# ArduinoV1Sch.net
KiCad netlist of a schematic drawn in Altium Designer
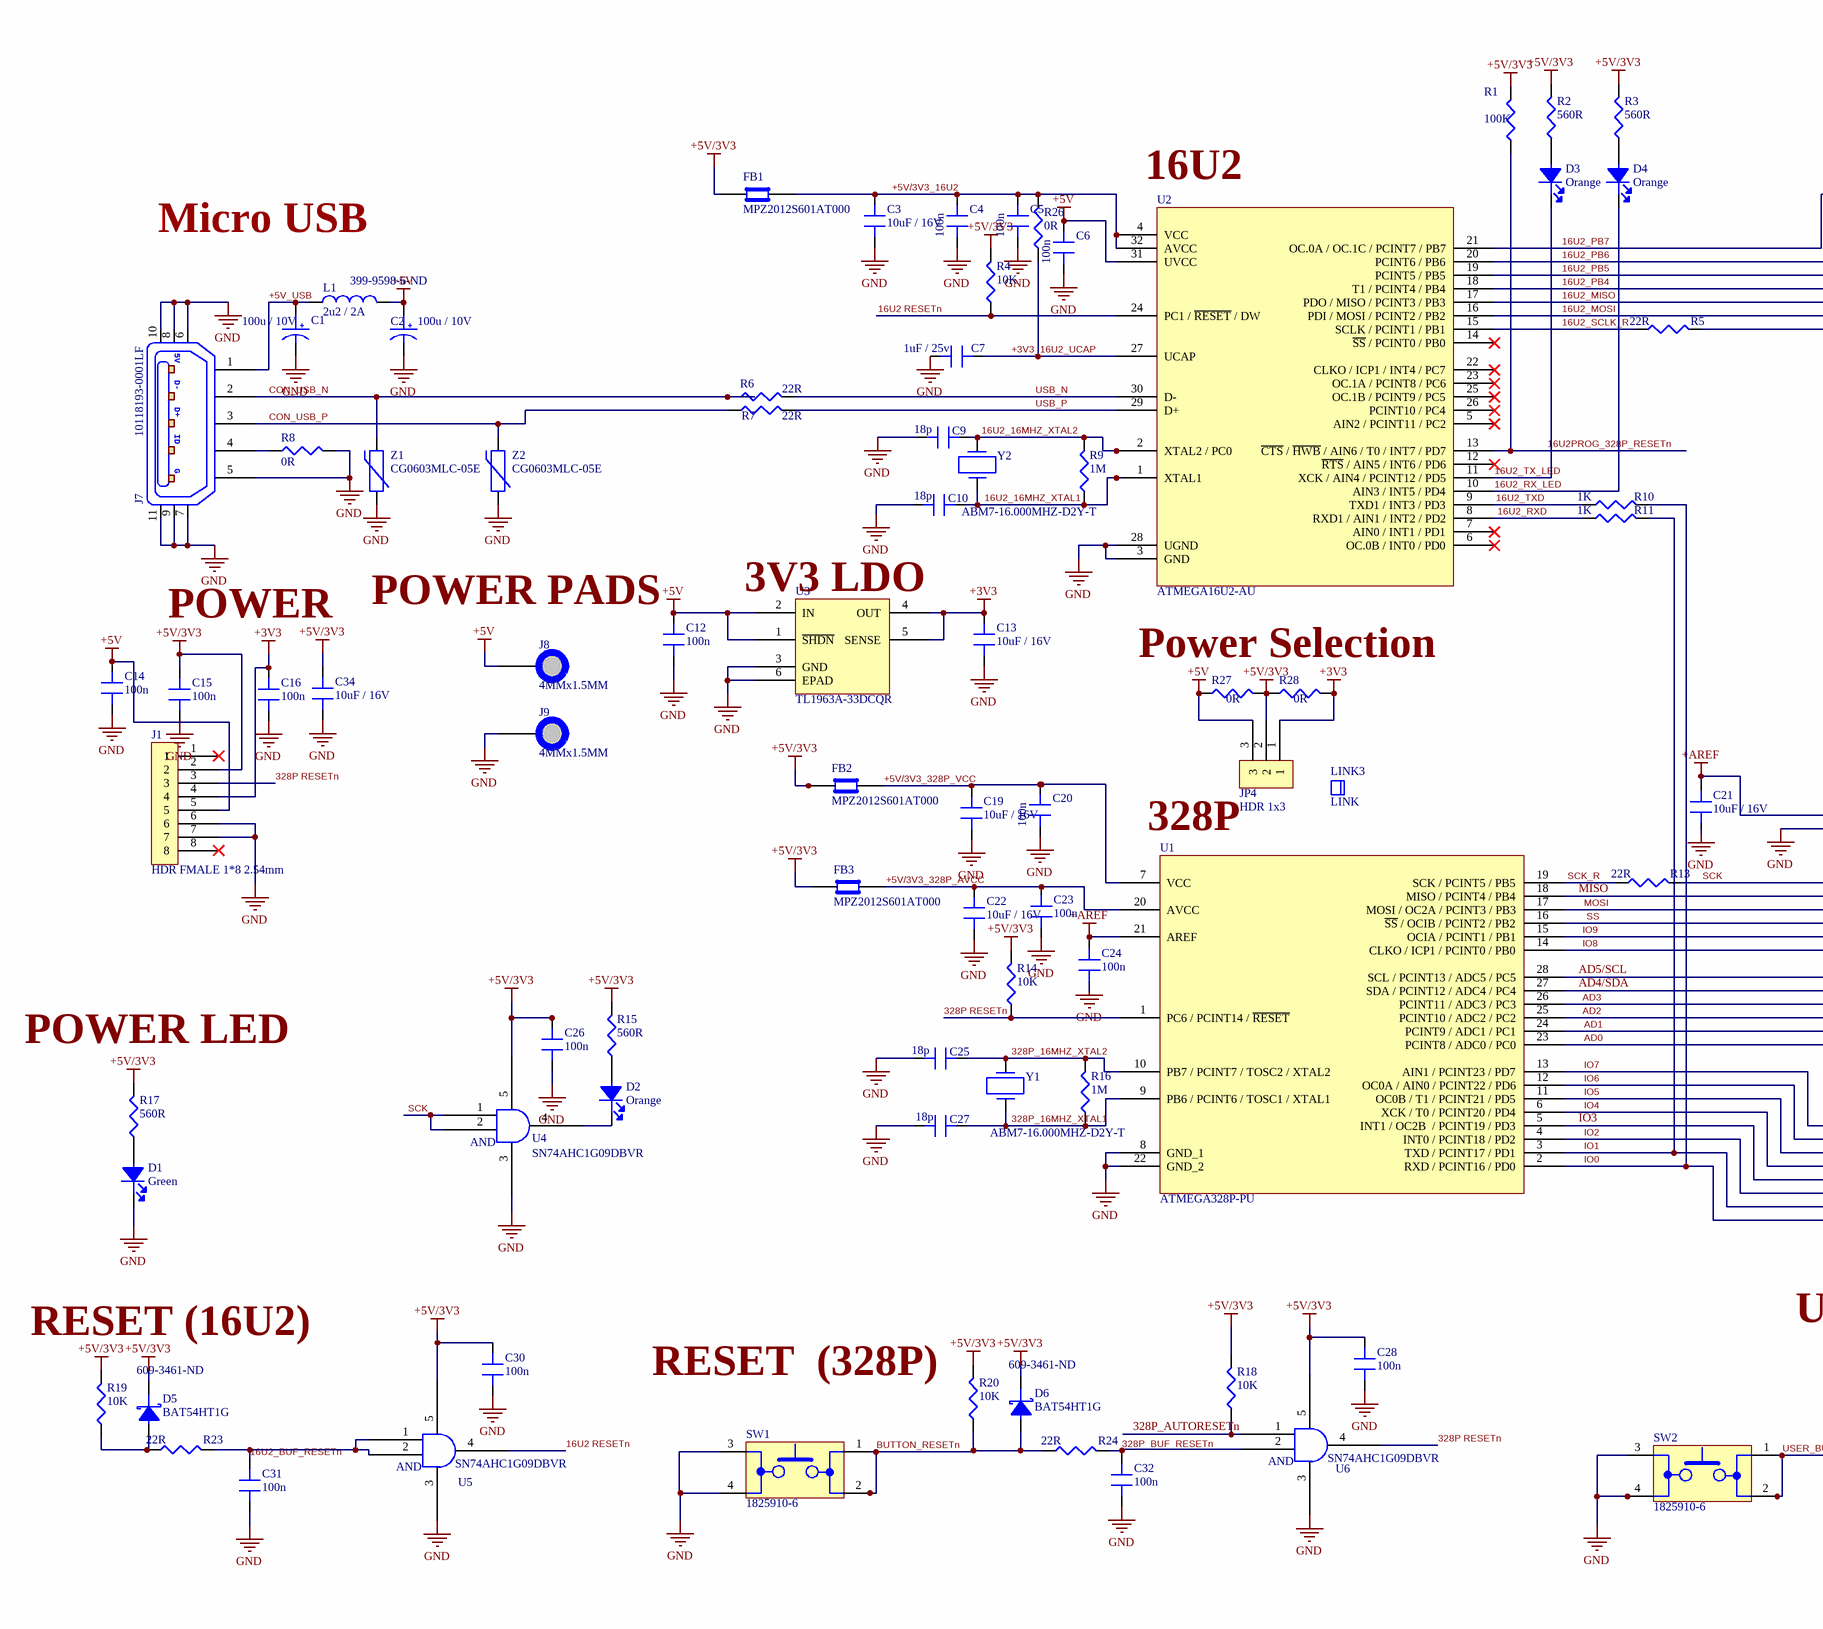
[diagram p0: ArduinoV1Sch.SchDoc, left]
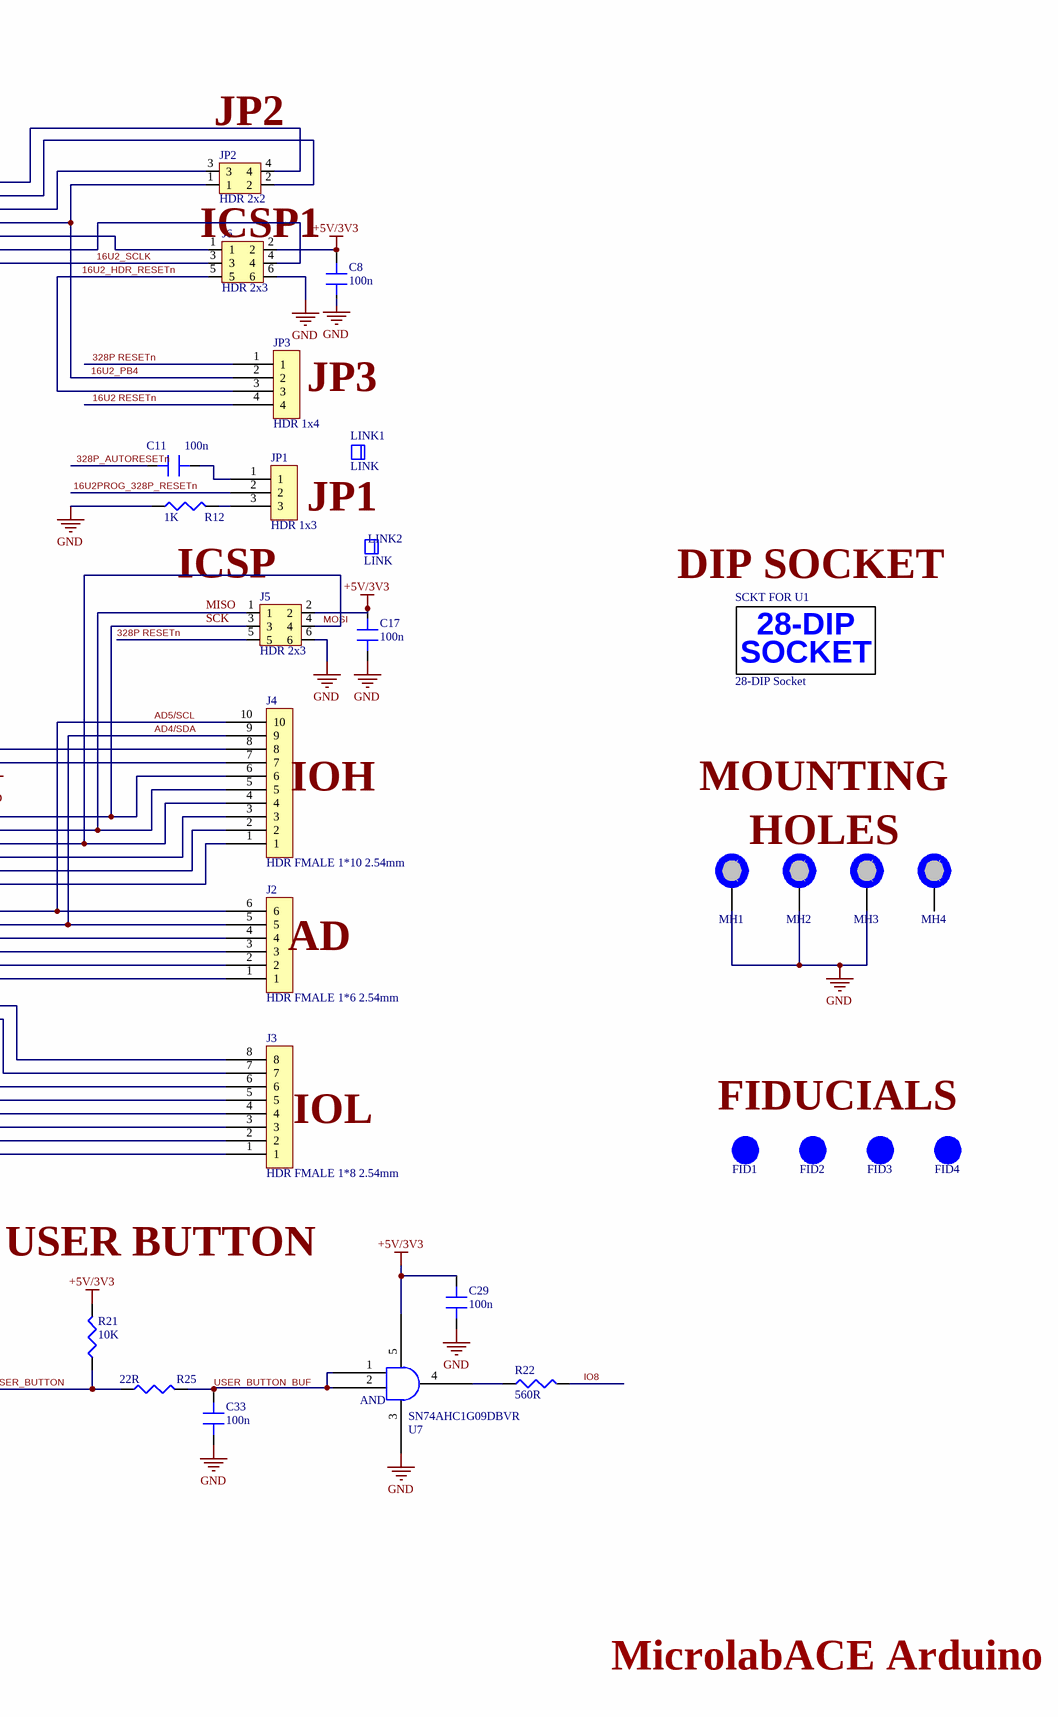
[diagram p1: ArduinoV1Sch.SchDoc, right]

(export (version "E")
  (design (tool "Eeschema 10.0.6"))
  (components
    (comp (ref "C1")
      (value "100u / 10V")
      (footprint "C_ALU_C_SIZE")
      (description "Cap Aluminum 100uF 10V 20% (5 X 5.4mm) SMD 50mA 1000 hr 85°C T/R")
      (fields
        (field (name "MANUFACTURER") "Panasonic")
        (field (name "MANUFACTURER PART NUMBER") "EEE-1AA101WR")
      )
      (libsource (lib "ArduinoV1Sch") (part "EEE-1AA101WR"))
    )
    (comp (ref "C2")
      (value "100u / 10V")
      (footprint "C_ALU_C_SIZE")
      (description "Cap Aluminum 100uF 10V 20% (5 X 5.4mm) SMD 50mA 1000 hr 85°C T/R")
      (fields
        (field (name "MANUFACTURER") "Panasonic")
        (field (name "MANUFACTURER PART NUMBER") "EEE-1AA101WR")
      )
      (libsource (lib "ArduinoV1Sch") (part "EEE-1AA101WR"))
    )
    (comp (ref "C3")
      (value "10uF / 16V")
      (footprint "C0805")
      (description "CAP CER 10UF 16V X5R 0805")
      (fields
        (field (name "MANUFACTURER") "TDK")
        (field (name "MANUFACTURER PART NUMBER") "CGA4J1X5R1C106M125AC")
      )
      (libsource (lib "ArduinoV1Sch") (part "CGA4J1X5R1C106M125AC"))
    )
    (comp (ref "C4")
      (value "100n")
      (footprint "C0805")
      (description "CAP CER 0.1UF 50V X7R 0805")
      (fields
        (field (name "MANUFACTURER") "TDK")
        (field (name "MANUFACTURER PART NUMBER") "C2012X7R1H104K085AA")
      )
      (libsource (lib "ArduinoV1Sch") (part "C2012X7R1H104K085AA"))
    )
    (comp (ref "C5")
      (value "100n")
      (footprint "C0805")
      (description "CAP CER 0.1UF 50V X7R 0805")
      (fields
        (field (name "MANUFACTURER") "TDK")
        (field (name "MANUFACTURER PART NUMBER") "C2012X7R1H104K085AA")
      )
      (libsource (lib "ArduinoV1Sch") (part "C2012X7R1H104K085AA"))
    )
    (comp (ref "C6")
      (value "100n")
      (footprint "C0805")
      (description "CAP CER 0.1UF 50V X7R 0805")
      (fields
        (field (name "MANUFACTURER") "TDK")
        (field (name "MANUFACTURER PART NUMBER") "C2012X7R1H104K085AA")
      )
      (libsource (lib "ArduinoV1Sch") (part "C2012X7R1H104K085AA"))
    )
    (comp (ref "C7")
      (value "1uF / 25v")
      (footprint "C0805")
      (description "CAP CER 1UF 25V X5R 0805")
      (fields
        (field (name "MANUFACTURER") "TDK")
        (field (name "MANUFACTURER PART NUMBER") "C2012X5R1E105K125AA")
      )
      (libsource (lib "ArduinoV1Sch") (part "C2012X5R1E105K125AA"))
    )
    (comp (ref "C8")
      (value "100n")
      (footprint "C0805")
      (description "CAP CER 0.1UF 50V X7R 0805")
      (fields
        (field (name "MANUFACTURER") "TDK")
        (field (name "MANUFACTURER PART NUMBER") "C2012X7R1H104K085AA")
      )
      (libsource (lib "ArduinoV1Sch") (part "C2012X7R1H104K085AA"))
    )
    (comp (ref "C9")
      (value "18p")
      (footprint "C0805")
      (fields
        (field (name "MANUFACTURER") "KEMET")
        (field (name "MANUFACTURER PART NUMBER") "C0805X180J5GAC7800")
      )
      (libsource (lib "ArduinoV1Sch") (part "C0805X180J5GAC7800"))
    )
    (comp (ref "C10")
      (value "18p")
      (footprint "C0805")
      (fields
        (field (name "MANUFACTURER") "KEMET")
        (field (name "MANUFACTURER PART NUMBER") "C0805X180J5GAC7800")
      )
      (libsource (lib "ArduinoV1Sch") (part "C0805X180J5GAC7800"))
    )
    (comp (ref "C11")
      (value "100n")
      (footprint "C0805")
      (description "CAP CER 0.1UF 50V X7R 0805")
      (fields
        (field (name "MANUFACTURER") "TDK")
        (field (name "MANUFACTURER PART NUMBER") "C2012X7R1H104K085AA")
      )
      (libsource (lib "ArduinoV1Sch") (part "C2012X7R1H104K085AA"))
    )
    (comp (ref "C12")
      (value "100n")
      (footprint "C0805")
      (description "CAP CER 0.1UF 50V X7R 0805")
      (fields
        (field (name "MANUFACTURER") "TDK")
        (field (name "MANUFACTURER PART NUMBER") "C2012X7R1H104K085AA")
      )
      (libsource (lib "ArduinoV1Sch") (part "C2012X7R1H104K085AA"))
    )
    (comp (ref "C13")
      (value "10uF / 16V")
      (footprint "C0805")
      (description "CAP CER 10UF 16V X5R 0805")
      (fields
        (field (name "MANUFACTURER") "TDK")
        (field (name "MANUFACTURER PART NUMBER") "CGA4J1X5R1C106M125AC")
      )
      (libsource (lib "ArduinoV1Sch") (part "CGA4J1X5R1C106M125AC"))
    )
    (comp (ref "C14")
      (value "100n")
      (footprint "C0805")
      (description "CAP CER 0.1UF 50V X7R 0805")
      (fields
        (field (name "MANUFACTURER") "TDK")
        (field (name "MANUFACTURER PART NUMBER") "C2012X7R1H104K085AA")
      )
      (libsource (lib "ArduinoV1Sch") (part "C2012X7R1H104K085AA"))
    )
    (comp (ref "C15")
      (value "100n")
      (footprint "C0805")
      (description "CAP CER 0.1UF 50V X7R 0805")
      (fields
        (field (name "MANUFACTURER") "TDK")
        (field (name "MANUFACTURER PART NUMBER") "C2012X7R1H104K085AA")
      )
      (libsource (lib "ArduinoV1Sch") (part "C2012X7R1H104K085AA"))
    )
    (comp (ref "C16")
      (value "100n")
      (footprint "C0805")
      (description "CAP CER 0.1UF 50V X7R 0805")
      (fields
        (field (name "MANUFACTURER") "TDK")
        (field (name "MANUFACTURER PART NUMBER") "C2012X7R1H104K085AA")
      )
      (libsource (lib "ArduinoV1Sch") (part "C2012X7R1H104K085AA"))
    )
    (comp (ref "C17")
      (value "100n")
      (footprint "C0805")
      (description "CAP CER 0.1UF 50V X7R 0805")
      (fields
        (field (name "MANUFACTURER") "TDK")
        (field (name "MANUFACTURER PART NUMBER") "C2012X7R1H104K085AA")
      )
      (libsource (lib "ArduinoV1Sch") (part "C2012X7R1H104K085AA"))
    )
    (comp (ref "C19")
      (value "10uF / 16V")
      (footprint "C0805")
      (description "CAP CER 10UF 16V X5R 0805")
      (fields
        (field (name "MANUFACTURER") "TDK")
        (field (name "MANUFACTURER PART NUMBER") "CGA4J1X5R1C106M125AC")
      )
      (libsource (lib "ArduinoV1Sch") (part "CGA4J1X5R1C106M125AC"))
    )
    (comp (ref "C20")
      (value "100n")
      (footprint "C0805")
      (description "CAP CER 0.1UF 50V X7R 0805")
      (fields
        (field (name "MANUFACTURER") "TDK")
        (field (name "MANUFACTURER PART NUMBER") "C2012X7R1H104K085AA")
      )
      (libsource (lib "ArduinoV1Sch") (part "C2012X7R1H104K085AA"))
    )
    (comp (ref "C21")
      (value "10uF / 16V")
      (footprint "C0805")
      (description "CAP CER 10UF 16V X5R 0805")
      (fields
        (field (name "MANUFACTURER") "TDK")
        (field (name "MANUFACTURER PART NUMBER") "CGA4J1X5R1C106M125AC")
      )
      (libsource (lib "ArduinoV1Sch") (part "CGA4J1X5R1C106M125AC"))
    )
    (comp (ref "C22")
      (value "10uF / 16V")
      (footprint "C0805")
      (description "CAP CER 10UF 16V X5R 0805")
      (fields
        (field (name "MANUFACTURER") "TDK")
        (field (name "MANUFACTURER PART NUMBER") "CGA4J1X5R1C106M125AC")
      )
      (libsource (lib "ArduinoV1Sch") (part "CGA4J1X5R1C106M125AC"))
    )
    (comp (ref "C23")
      (value "100n")
      (footprint "C0805")
      (description "CAP CER 0.1UF 50V X7R 0805")
      (fields
        (field (name "MANUFACTURER") "TDK")
        (field (name "MANUFACTURER PART NUMBER") "C2012X7R1H104K085AA")
      )
      (libsource (lib "ArduinoV1Sch") (part "C2012X7R1H104K085AA"))
    )
    (comp (ref "C24")
      (value "100n")
      (footprint "C0805")
      (description "CAP CER 0.1UF 50V X7R 0805")
      (fields
        (field (name "MANUFACTURER") "TDK")
        (field (name "MANUFACTURER PART NUMBER") "C2012X7R1H104K085AA")
      )
      (libsource (lib "ArduinoV1Sch") (part "C2012X7R1H104K085AA"))
    )
    (comp (ref "C25")
      (value "18p")
      (footprint "C0805")
      (fields
        (field (name "MANUFACTURER") "KEMET")
        (field (name "MANUFACTURER PART NUMBER") "C0805X180J5GAC7800")
      )
      (libsource (lib "ArduinoV1Sch") (part "C0805X180J5GAC7800"))
    )
    (comp (ref "C26")
      (value "100n")
      (footprint "C0805")
      (description "CAP CER 0.1UF 50V X7R 0805")
      (fields
        (field (name "MANUFACTURER") "TDK")
        (field (name "MANUFACTURER PART NUMBER") "C2012X7R1H104K085AA")
      )
      (libsource (lib "ArduinoV1Sch") (part "C2012X7R1H104K085AA"))
    )
    (comp (ref "C27")
      (value "18p")
      (footprint "C0805")
      (fields
        (field (name "MANUFACTURER") "KEMET")
        (field (name "MANUFACTURER PART NUMBER") "C0805X180J5GAC7800")
      )
      (libsource (lib "ArduinoV1Sch") (part "C0805X180J5GAC7800"))
    )
    (comp (ref "C28")
      (value "100n")
      (footprint "C0805")
      (description "CAP CER 0.1UF 50V X7R 0805")
      (fields
        (field (name "MANUFACTURER") "TDK")
        (field (name "MANUFACTURER PART NUMBER") "C2012X7R1H104K085AA")
      )
      (libsource (lib "ArduinoV1Sch") (part "C2012X7R1H104K085AA"))
    )
    (comp (ref "C29")
      (value "100n")
      (footprint "C0805")
      (description "CAP CER 0.1UF 50V X7R 0805")
      (fields
        (field (name "MANUFACTURER") "TDK")
        (field (name "MANUFACTURER PART NUMBER") "C2012X7R1H104K085AA")
      )
      (libsource (lib "ArduinoV1Sch") (part "C2012X7R1H104K085AA"))
    )
    (comp (ref "C30")
      (value "100n")
      (footprint "C0805")
      (description "CAP CER 0.1UF 50V X7R 0805")
      (fields
        (field (name "MANUFACTURER") "TDK")
        (field (name "MANUFACTURER PART NUMBER") "C2012X7R1H104K085AA")
      )
      (libsource (lib "ArduinoV1Sch") (part "C2012X7R1H104K085AA"))
    )
    (comp (ref "C31")
      (value "100n")
      (footprint "C0805")
      (description "CAP CER 0.1UF 50V X7R 0805")
      (fields
        (field (name "MANUFACTURER") "TDK")
        (field (name "MANUFACTURER PART NUMBER") "C2012X7R1H104K085AA")
      )
      (libsource (lib "ArduinoV1Sch") (part "C2012X7R1H104K085AA"))
    )
    (comp (ref "C32")
      (value "100n")
      (footprint "C0805")
      (description "CAP CER 0.1UF 50V X7R 0805")
      (fields
        (field (name "MANUFACTURER") "TDK")
        (field (name "MANUFACTURER PART NUMBER") "C2012X7R1H104K085AA")
      )
      (libsource (lib "ArduinoV1Sch") (part "C2012X7R1H104K085AA"))
    )
    (comp (ref "C33")
      (value "100n")
      (footprint "C0805")
      (description "CAP CER 0.1UF 50V X7R 0805")
      (fields
        (field (name "MANUFACTURER") "TDK")
        (field (name "MANUFACTURER PART NUMBER") "C2012X7R1H104K085AA")
      )
      (libsource (lib "ArduinoV1Sch") (part "C2012X7R1H104K085AA"))
    )
    (comp (ref "C34")
      (value "10uF / 16V")
      (footprint "C0805")
      (description "CAP CER 10UF 16V X5R 0805")
      (fields
        (field (name "MANUFACTURER") "TDK")
        (field (name "MANUFACTURER PART NUMBER") "CGA4J1X5R1C106M125AC")
      )
      (libsource (lib "ArduinoV1Sch") (part "CGA4J1X5R1C106M125AC"))
    )
    (comp (ref "D1")
      (value "Green")
      (footprint "LED_0603")
      (description "LED Uni-Color Green 572nm 2-Pin Chip 0603(1608Metric) T/R")
      (fields
        (field (name "MANUFACTURER") "Osram Opto")
        (field (name "MANUFACTURER PART NUMBER") "LGL29K-G2J1-24-Z")
      )
      (libsource (lib "ArduinoV1Sch") (part "LGL29K-G2J1-24-Z"))
    )
    (comp (ref "D2")
      (value "Orange")
      (footprint "LED_0603")
      (description "LED ORANGE DIFFUSED 0603 SMD")
      (fields
        (field (name "MANUFACTURER") "Osram Opto")
        (field (name "MANUFACTURER PART NUMBER") "LOL29K-H2K1-24-Z")
      )
      (libsource (lib "ArduinoV1Sch") (part "LOL29K-H2K1-24-Z"))
    )
    (comp (ref "D3")
      (value "Orange")
      (footprint "LED_0603")
      (description "LED ORANGE DIFFUSED 0603 SMD")
      (fields
        (field (name "MANUFACTURER") "Osram Opto")
        (field (name "MANUFACTURER PART NUMBER") "LOL29K-H2K1-24-Z")
      )
      (libsource (lib "ArduinoV1Sch") (part "LOL29K-H2K1-24-Z"))
    )
    (comp (ref "D4")
      (value "Orange")
      (footprint "LED_0603")
      (description "LED ORANGE DIFFUSED 0603 SMD")
      (fields
        (field (name "MANUFACTURER") "Osram Opto")
        (field (name "MANUFACTURER PART NUMBER") "LOL29K-H2K1-24-Z")
      )
      (libsource (lib "ArduinoV1Sch") (part "LOL29K-H2K1-24-Z"))
    )
    (comp (ref "D5")
      (value "BAT54HT1G")
      (footprint "SOD323")
      (description "DIODE SCHOTTKY 30V 200MA SOD323")
      (fields
        (field (name "MANUFACTURER") "ON Semiconductor / Fairchild")
        (field (name "SUPPLIER PART NUMBER 2") "609-3461-ND")
      )
      (libsource (lib "ArduinoV1Sch") (part "BAT54HT1G"))
    )
    (comp (ref "D6")
      (value "BAT54HT1G")
      (footprint "SOD323")
      (description "DIODE SCHOTTKY 30V 200MA SOD323")
      (fields
        (field (name "MANUFACTURER") "ON Semiconductor / Fairchild")
        (field (name "SUPPLIER PART NUMBER 2") "609-3461-ND")
      )
      (libsource (lib "ArduinoV1Sch") (part "BAT54HT1G"))
    )
    (comp (ref "FB1")
      (value "MPZ2012S601AT000")
      (footprint "C0805")
      (description "Ferrite Beads Multi-Layer Power 600Ohm 25% 100MHz 2A 100mOhm DCR 0805 T/R")
      (fields (field (name "MANUFACTURER") "TDK"))
      (libsource (lib "ArduinoV1Sch") (part "MPZ2012S601AT000"))
    )
    (comp (ref "FB2")
      (value "MPZ2012S601AT000")
      (footprint "C0805")
      (description "Ferrite Beads Multi-Layer Power 600Ohm 25% 100MHz 2A 100mOhm DCR 0805 T/R")
      (fields (field (name "MANUFACTURER") "TDK"))
      (libsource (lib "ArduinoV1Sch") (part "MPZ2012S601AT000"))
    )
    (comp (ref "FB3")
      (value "MPZ2012S601AT000")
      (footprint "C0805")
      (description "Ferrite Beads Multi-Layer Power 600Ohm 25% 100MHz 2A 100mOhm DCR 0805 T/R")
      (fields (field (name "MANUFACTURER") "TDK"))
      (libsource (lib "ArduinoV1Sch") (part "MPZ2012S601AT000"))
    )
    (comp (ref "FID1")
      (value "FID_1MMC")
      (footprint "FID_40x120D")
      (description "Fiducial 40mil Diameter 120mil Mask")
      (libsource (lib "ArduinoV1Sch") (part "FID_1MMC"))
    )
    (comp (ref "FID2")
      (value "FID_1MMC")
      (footprint "FID_40x120D")
      (description "Fiducial 40mil Diameter 120mil Mask")
      (libsource (lib "ArduinoV1Sch") (part "FID_1MMC"))
    )
    (comp (ref "FID3")
      (value "FID_1MMC")
      (footprint "FID_40x120D")
      (description "Fiducial 40mil Diameter 120mil Mask")
      (libsource (lib "ArduinoV1Sch") (part "FID_1MMC"))
    )
    (comp (ref "FID4")
      (value "FID_1MMC")
      (footprint "FID_40x120D")
      (description "Fiducial 40mil Diameter 120mil Mask")
      (libsource (lib "ArduinoV1Sch") (part "FID_1MMC"))
    )
    (comp (ref "J1")
      (value "HDR FMALE 1*8 2.54mm")
      (footprint "Hdr_Female_1*8_2.54mm")
      (description "08-WAY SIL VERT SOCKET L/FREE")
      (fields (field (name "MANUFACTURER") "Harwin") (field (name "MANUFACTURER PART NUMBER") "M20-7820842"))
      (libsource (lib "") (part "M20-7820842_1"))
    )
    (comp (ref "J2")
      (value "HDR FMALE 1*6 2.54mm")
      (footprint "Hdr_Female_1*6_2.54mm")
      (description "06-WAY SIL VERT SOCKET L/FREE")
      (fields (field (name "MANUFACTURER") "Harwin") (field (name "MANUFACTURER PART NUMBER") "M20-7820646"))
      (libsource (lib "ArduinoV1Sch") (part "M20-7820646"))
    )
    (comp (ref "J3")
      (value "HDR FMALE 1*8 2.54mm")
      (footprint "Hdr_Female_1*8_2.54mm")
      (description "08-WAY SIL VERT SOCKET L/FREE")
      (fields (field (name "MANUFACTURER") "Harwin") (field (name "MANUFACTURER PART NUMBER") "M20-7820842"))
      (libsource (lib "ArduinoV1Sch") (part "M20-7820842"))
    )
    (comp (ref "J4")
      (value "HDR FMALE 1*10 2.54mm")
      (footprint "Hdr_Female_1*10_2.54mm")
      (description "10-WAY SIL VERT SOCKET L/FREE")
      (fields (field (name "MANUFACTURER") "Harwin") (field (name "MANUFACTURER PART NUMBER") "M20-7821046"))
      (libsource (lib "ArduinoV1Sch") (part "M20-7821046"))
    )
    (comp (ref "J5")
      (value "HDR 2x3")
      (footprint "HDR_2x3_2.54MM")
      (description "CONN HEADER VERT 6POS 2.54MM")
      (fields
        (field (name "MANUFACTURER") "Amphenol FCI")
        (field (name "MANUFACTURER PART NUMBER") "67997-106HLF")
      )
      (libsource (lib "ArduinoV1Sch") (part "67997-106HLF"))
    )
    (comp (ref "J6")
      (value "HDR 2x3")
      (footprint "HDR_2x3_2.54MM")
      (description "CONN HEADER VERT 6POS 2.54MM")
      (fields
        (field (name "MANUFACTURER") "Amphenol FCI")
        (field (name "MANUFACTURER PART NUMBER") "67997-106HLF")
      )
      (libsource (lib "ArduinoV1Sch") (part "67997-106HLF"))
    )
    (comp (ref "J7")
      (value "10118193-0001LF")
      (footprint "10118193")
      (description "CONN RCPT USB2.0 MICRO B SMD R/A")
      (fields (field (name "MANUFACTURER") "Amphenol FCI"))
      (libsource (lib "ArduinoV1Sch") (part "10118193-0001LF"))
    )
    (comp (ref "J8")
      (value "4MMx1.5MM")
      (footprint "PAD_WITH_HOLE_4MMx1.5MM")
      (description "PAD_WITH_HOLE_4MMx1.5MM")
      (libsource (lib "ArduinoV1Sch") (part "PAD_WITH_HOLE_4MMx1.5MM"))
    )
    (comp (ref "J9")
      (value "4MMx1.5MM")
      (footprint "PAD_WITH_HOLE_4MMx1.5MM")
      (description "PAD_WITH_HOLE_4MMx1.5MM")
      (libsource (lib "ArduinoV1Sch") (part "PAD_WITH_HOLE_4MMx1.5MM"))
    )
    (comp (ref "JP1")
      (value "HDR 1x3")
      (footprint "Hdr_1*3_2.54mm")
      (description "CONN HEADER VERT 3POS 2.54MM")
      (fields
        (field (name "MANUFACTURER") "Amphenol FCI")
        (field (name "MANUFACTURER PART NUMBER") "68000-103HLF")
      )
      (libsource (lib "") (part "68000-103HLF_1"))
    )
    (comp (ref "JP2")
      (value "HDR 2x2")
      (footprint "HDR_2x2_2.54MM")
      (description "CONN HEADER VERT 4POS 2.54MM")
      (fields
        (field (name "MANUFACTURER") "Amphenol FCI")
        (field (name "MANUFACTURER PART NUMBER") "68602-204HLF")
      )
      (libsource (lib "ArduinoV1Sch") (part "68602-204HLF"))
    )
    (comp (ref "JP3")
      (value "HDR 1x4")
      (footprint "Hdr_1*4_2.54mm")
      (description "CONN HEADER VERT 4POS 2.54MM")
      (fields
        (field (name "MANUFACTURER") "Amphenol FCI")
        (field (name "MANUFACTURER PART NUMBER") "68001-204HLF")
      )
      (libsource (lib "ArduinoV1Sch") (part "68001-204HLF"))
    )
    (comp (ref "JP4")
      (value "HDR 1x3")
      (footprint "Hdr_1*3_2.54mm")
      (description "CONN HEADER VERT 3POS 2.54MM")
      (fields
        (field (name "MANUFACTURER") "Amphenol FCI")
        (field (name "MANUFACTURER PART NUMBER") "68000-103HLF")
      )
      (libsource (lib "ArduinoV1Sch") (part "68000-103HLF"))
    )
    (comp (ref "L1")
      (value "2u2 / 2A")
      (footprint "C1210_IND")
      (description "FIXED IND 2.2UH 2A 80 MOHM SMD")
      (fields
        (field (name "MANUFACTURER") "KEMET")
        (field (name "MANUFACTURER PART NUMBER") "L1210R2R2MDWIT")
        (field (name "SUPPLIER PART NUMBER 1") "399-9598-6-ND")
      )
      (libsource (lib "ArduinoV1Sch") (part "L1210R2R2MDWIT"))
    )
    (comp (ref "LINK1")
      (value "LINK")
      (description "CONN JUMPER SHORTING .100\" GOLD")
      (fields
        (field (name "MANUFACTURER") "Sullins")
        (field (name "MANUFACTURER PART NUMBER") "QPC02SXGN-RC")
      )
      (libsource (lib "ArduinoV1Sch") (part "QPC02SXGN-RC"))
    )
    (comp (ref "LINK2")
      (value "LINK")
      (description "CONN JUMPER SHORTING .100\" GOLD")
      (fields
        (field (name "MANUFACTURER") "Sullins")
        (field (name "MANUFACTURER PART NUMBER") "QPC02SXGN-RC")
      )
      (libsource (lib "ArduinoV1Sch") (part "QPC02SXGN-RC"))
    )
    (comp (ref "LINK3")
      (value "LINK")
      (description "CONN JUMPER SHORTING .100\" GOLD")
      (fields
        (field (name "MANUFACTURER") "Sullins")
        (field (name "MANUFACTURER PART NUMBER") "QPC02SXGN-RC")
      )
      (libsource (lib "ArduinoV1Sch") (part "QPC02SXGN-RC"))
    )
    (comp (ref "MH1")
      (value "MH_7.4MMC_3.2MMD")
      (footprint "MH_7.4MMC_3.2MMD")
      (description "Mounting Hole 7..4mm Diameter_3.2mm Drill")
      (libsource (lib "ArduinoV1Sch") (part "MH_7.4MMC_3.2MMD"))
    )
    (comp (ref "MH2")
      (value "MH_7.4MMC_3.2MMD")
      (footprint "MH_7.4MMC_3.2MMD")
      (description "Mounting Hole 7..4mm Diameter_3.2mm Drill")
      (libsource (lib "ArduinoV1Sch") (part "MH_7.4MMC_3.2MMD"))
    )
    (comp (ref "MH3")
      (value "MH_7.4MMC_3.2MMD")
      (footprint "MH_7.4MMC_3.2MMD")
      (description "Mounting Hole 7..4mm Diameter_3.2mm Drill")
      (libsource (lib "ArduinoV1Sch") (part "MH_7.4MMC_3.2MMD"))
    )
    (comp (ref "MH4")
      (value "MH_7.4MMNC_3.2MMD")
      (footprint "MH_7.4MMND_3.2MMD_NON_COPPER_NPTH")
      (description "Mounting Hole 7.4mm Diameter (Non Copper), 3.2mm Drill NPTH")
      (libsource (lib "ArduinoV1Sch") (part "MH_7.4MMNC_3.2MMD"))
    )
    (comp (ref "R1")
      (value "100K")
      (footprint "R0805")
      (description "RES SMD 100K OHM 5% 1/8W 0805")
      (fields
        (field (name "MANUFACTURER") "Yageo")
        (field (name "MANUFACTURER PART NUMBER") "RC0805JR-07100KL")
      )
      (libsource (lib "ArduinoV1Sch") (part "RC0805JR-07100KL"))
    )
    (comp (ref "R2")
      (value "560R")
      (footprint "R0805")
      (description "Yageo RC0805 Series Thick Film Surface Mount Resistor 0805 Case 560 1% 0.125W 100ppm/C")
      (fields
        (field (name "MANUFACTURER") "Yageo Phycomp")
        (field (name "MANUFACTURER PART NUMBER") "RC0805FR-07560RL")
      )
      (libsource (lib "ArduinoV1Sch") (part "RC0805FR-07560RL"))
    )
    (comp (ref "R3")
      (value "560R")
      (footprint "R0805")
      (description "Yageo RC0805 Series Thick Film Surface Mount Resistor 0805 Case 560 1% 0.125W 100ppm/C")
      (fields
        (field (name "MANUFACTURER") "Yageo Phycomp")
        (field (name "MANUFACTURER PART NUMBER") "RC0805FR-07560RL")
      )
      (libsource (lib "ArduinoV1Sch") (part "RC0805FR-07560RL"))
    )
    (comp (ref "R4")
      (value "10K")
      (footprint "R0805")
      (description "RES SMD 10K OHM 1% 1/8W 0805")
      (fields
        (field (name "MANUFACTURER") "Yageo")
        (field (name "MANUFACTURER PART NUMBER") "RC0805FR-0710KL")
      )
      (libsource (lib "ArduinoV1Sch") (part "RC0805FR-0710KL"))
    )
    (comp (ref "R5")
      (value "22R")
      (footprint "R0805")
      (description "RES SMD 22 OHM 1% 1/8W 0805")
      (fields
        (field (name "MANUFACTURER") "Yageo")
        (field (name "MANUFACTURER PART NUMBER") "RC0805FR-0722RL")
      )
      (libsource (lib "ArduinoV1Sch") (part "RC0805FR-0722RL"))
    )
    (comp (ref "R6")
      (value "22R")
      (footprint "R0805")
      (description "RES SMD 22 OHM 1% 1/8W 0805")
      (fields
        (field (name "MANUFACTURER") "Yageo")
        (field (name "MANUFACTURER PART NUMBER") "RC0805FR-0722RL")
      )
      (libsource (lib "ArduinoV1Sch") (part "RC0805FR-0722RL"))
    )
    (comp (ref "R7")
      (value "22R")
      (footprint "R0805")
      (description "RES SMD 22 OHM 1% 1/8W 0805")
      (fields
        (field (name "MANUFACTURER") "Yageo")
        (field (name "MANUFACTURER PART NUMBER") "RC0805FR-0722RL")
      )
      (libsource (lib "ArduinoV1Sch") (part "RC0805FR-0722RL"))
    )
    (comp (ref "R8")
      (value "0R")
      (footprint "R0805")
      (description "RES SMD 0 OHM JUMPER 1/8W 0805")
      (fields
        (field (name "MANUFACTURER") "Yageo")
        (field (name "MANUFACTURER PART NUMBER") "RC0805JR-070RL")
      )
      (libsource (lib "ArduinoV1Sch") (part "RC0805JR-070RL"))
    )
    (comp (ref "R9")
      (value "1M")
      (footprint "R0805")
      (description "RES SMD 1M OHM 1% 1/8W 0805")
      (fields
        (field (name "MANUFACTURER") "Yageo Phycomp")
        (field (name "MANUFACTURER PART NUMBER") "RC0805FR-071ML")
      )
      (libsource (lib "ArduinoV1Sch") (part "RC0805FR-071ML"))
    )
    (comp (ref "R10")
      (value "1K")
      (footprint "R0805")
      (description "RES SMD 1K OHM 1% 1/8W 0805")
      (fields
        (field (name "MANUFACTURER") "Yageo Phycomp")
        (field (name "MANUFACTURER PART NUMBER") "RC0805FR-071KL")
      )
      (libsource (lib "ArduinoV1Sch") (part "RC0805FR-071KL"))
    )
    (comp (ref "R11")
      (value "1K")
      (footprint "R0805")
      (description "RES SMD 1K OHM 1% 1/8W 0805")
      (fields
        (field (name "MANUFACTURER") "Yageo Phycomp")
        (field (name "MANUFACTURER PART NUMBER") "RC0805FR-071KL")
      )
      (libsource (lib "ArduinoV1Sch") (part "RC0805FR-071KL"))
    )
    (comp (ref "R12")
      (value "1K")
      (footprint "R0805")
      (description "RES SMD 1K OHM 1% 1/8W 0805")
      (fields
        (field (name "MANUFACTURER") "Yageo Phycomp")
        (field (name "MANUFACTURER PART NUMBER") "RC0805FR-071KL")
      )
      (libsource (lib "ArduinoV1Sch") (part "RC0805FR-071KL"))
    )
    (comp (ref "R13")
      (value "22R")
      (footprint "R0805")
      (description "RES SMD 22 OHM 1% 1/8W 0805")
      (fields
        (field (name "MANUFACTURER") "Yageo")
        (field (name "MANUFACTURER PART NUMBER") "RC0805FR-0722RL")
      )
      (libsource (lib "ArduinoV1Sch") (part "RC0805FR-0722RL"))
    )
    (comp (ref "R14")
      (value "10K")
      (footprint "R0805")
      (description "RES SMD 10K OHM 1% 1/8W 0805")
      (fields
        (field (name "MANUFACTURER") "Yageo")
        (field (name "MANUFACTURER PART NUMBER") "RC0805FR-0710KL")
      )
      (libsource (lib "ArduinoV1Sch") (part "RC0805FR-0710KL"))
    )
    (comp (ref "R15")
      (value "560R")
      (footprint "R0805")
      (description "Yageo RC0805 Series Thick Film Surface Mount Resistor 0805 Case 560 1% 0.125W 100ppm/C")
      (fields
        (field (name "MANUFACTURER") "Yageo Phycomp")
        (field (name "MANUFACTURER PART NUMBER") "RC0805FR-07560RL")
      )
      (libsource (lib "ArduinoV1Sch") (part "RC0805FR-07560RL"))
    )
    (comp (ref "R16")
      (value "1M")
      (footprint "R0805")
      (description "RES SMD 1M OHM 1% 1/8W 0805")
      (fields
        (field (name "MANUFACTURER") "Yageo Phycomp")
        (field (name "MANUFACTURER PART NUMBER") "RC0805FR-071ML")
      )
      (libsource (lib "ArduinoV1Sch") (part "RC0805FR-071ML"))
    )
    (comp (ref "R17")
      (value "560R")
      (footprint "R0805")
      (description "Yageo RC0805 Series Thick Film Surface Mount Resistor 0805 Case 560 1% 0.125W 100ppm/C")
      (fields
        (field (name "MANUFACTURER") "Yageo Phycomp")
        (field (name "MANUFACTURER PART NUMBER") "RC0805FR-07560RL")
      )
      (libsource (lib "ArduinoV1Sch") (part "RC0805FR-07560RL"))
    )
    (comp (ref "R18")
      (value "10K")
      (footprint "R0805")
      (description "RES SMD 10K OHM 1% 1/8W 0805")
      (fields
        (field (name "MANUFACTURER") "Yageo")
        (field (name "MANUFACTURER PART NUMBER") "RC0805FR-0710KL")
      )
      (libsource (lib "ArduinoV1Sch") (part "RC0805FR-0710KL"))
    )
    (comp (ref "R19")
      (value "10K")
      (footprint "R0805")
      (description "RES SMD 10K OHM 1% 1/8W 0805")
      (fields
        (field (name "MANUFACTURER") "Yageo")
        (field (name "MANUFACTURER PART NUMBER") "RC0805FR-0710KL")
      )
      (libsource (lib "ArduinoV1Sch") (part "RC0805FR-0710KL"))
    )
    (comp (ref "R20")
      (value "10K")
      (footprint "R0805")
      (description "RES SMD 10K OHM 1% 1/8W 0805")
      (fields
        (field (name "MANUFACTURER") "Yageo")
        (field (name "MANUFACTURER PART NUMBER") "RC0805FR-0710KL")
      )
      (libsource (lib "ArduinoV1Sch") (part "RC0805FR-0710KL"))
    )
    (comp (ref "R21")
      (value "10K")
      (footprint "R0805")
      (description "RES SMD 10K OHM 1% 1/8W 0805")
      (fields
        (field (name "MANUFACTURER") "Yageo")
        (field (name "MANUFACTURER PART NUMBER") "RC0805FR-0710KL")
      )
      (libsource (lib "ArduinoV1Sch") (part "RC0805FR-0710KL"))
    )
    (comp (ref "R22")
      (value "560R")
      (footprint "R0805")
      (description "Yageo RC0805 Series Thick Film Surface Mount Resistor 0805 Case 560 1% 0.125W 100ppm/C")
      (fields
        (field (name "MANUFACTURER") "Yageo Phycomp")
        (field (name "MANUFACTURER PART NUMBER") "RC0805FR-07560RL")
      )
      (libsource (lib "ArduinoV1Sch") (part "RC0805FR-07560RL"))
    )
    (comp (ref "R23")
      (value "22R")
      (footprint "R0805")
      (description "RES SMD 22 OHM 1% 1/8W 0805")
      (fields
        (field (name "MANUFACTURER") "Yageo")
        (field (name "MANUFACTURER PART NUMBER") "RC0805FR-0722RL")
      )
      (libsource (lib "ArduinoV1Sch") (part "RC0805FR-0722RL"))
    )
    (comp (ref "R24")
      (value "22R")
      (footprint "R0805")
      (description "RES SMD 22 OHM 1% 1/8W 0805")
      (fields
        (field (name "MANUFACTURER") "Yageo")
        (field (name "MANUFACTURER PART NUMBER") "RC0805FR-0722RL")
      )
      (libsource (lib "ArduinoV1Sch") (part "RC0805FR-0722RL"))
    )
    (comp (ref "R25")
      (value "22R")
      (footprint "R0805")
      (description "RES SMD 22 OHM 1% 1/8W 0805")
      (fields
        (field (name "MANUFACTURER") "Yageo")
        (field (name "MANUFACTURER PART NUMBER") "RC0805FR-0722RL")
      )
      (libsource (lib "ArduinoV1Sch") (part "RC0805FR-0722RL"))
    )
    (comp (ref "R26")
      (value "0R")
      (footprint "R0805")
      (description "RES SMD 0 OHM JUMPER 1/8W 0805")
      (fields
        (field (name "MANUFACTURER") "Yageo")
        (field (name "MANUFACTURER PART NUMBER") "RC0805JR-070RL")
      )
      (libsource (lib "ArduinoV1Sch") (part "RC0805JR-070RL"))
    )
    (comp (ref "R27")
      (value "0R")
      (footprint "R0805")
      (description "RES SMD 0 OHM JUMPER 1/8W 0805")
      (fields
        (field (name "MANUFACTURER") "Yageo")
        (field (name "MANUFACTURER PART NUMBER") "RC0805JR-070RL")
      )
      (libsource (lib "ArduinoV1Sch") (part "RC0805JR-070RL"))
    )
    (comp (ref "R28")
      (value "0R")
      (footprint "R0805")
      (description "RES SMD 0 OHM JUMPER 1/8W 0805")
      (fields
        (field (name "MANUFACTURER") "Yageo")
        (field (name "MANUFACTURER PART NUMBER") "RC0805JR-070RL")
      )
      (libsource (lib "ArduinoV1Sch") (part "RC0805JR-070RL"))
    )
    (comp (ref "SCKT FOR U1")
      (value "28-DIP Socket")
      (footprint "28_DIP_7.63mm_SOCKET")
      (description "CONN IC DIP SOCKET 28POS TIN")
      (fields (field (name "MANUFACTURER") "3M") (field (name "MANUFACTURER PART NUMBER") "4828-3004-CP"))
      (libsource (lib "ArduinoV1Sch") (part "4828-3004-CP"))
    )
    (comp (ref "SW1")
      (value "1825910-6")
      (footprint "1825910-6")
      (description "ALCOSWITCH - TE CONNECTIVITY - 1825910-6 - TACT SWITCH, SPST, 0.05A, 24VDC, SOLDER")
      (fields (field (name "MANUFACTURER") "TE Connectivity Alcoswitch"))
      (libsource (lib "ArduinoV1Sch") (part "1825910-6"))
    )
    (comp (ref "SW2")
      (value "1825910-6")
      (footprint "1825910-6")
      (description "ALCOSWITCH - TE CONNECTIVITY - 1825910-6 - TACT SWITCH, SPST, 0.05A, 24VDC, SOLDER")
      (fields (field (name "MANUFACTURER") "TE Connectivity Alcoswitch"))
      (libsource (lib "ArduinoV1Sch") (part "1825910-6"))
    )
    (comp (ref "U1")
      (value "ATMEGA328P-PU")
      (footprint "20_DIP_7.62mm")
      (fields (field (name "MANUFACTURER") "Microchip / Atmel"))
      (libsource (lib "ArduinoV1Sch") (part "ATMEGA328P-PU"))
    )
    (comp (ref "U2")
      (value "ATMEGA16U2-AU")
      (footprint "TQFP32")
      (description "MICROCHIP - ATMEGA16U2-AU - MCU, 8BIT, MEGAAVR, 16MHZ, TQFP-32")
      (fields (field (name "MANUFACTURER") "Microchip / Atmel"))
      (libsource (lib "ArduinoV1Sch") (part "ATMEGA16U2-AU"))
    )
    (comp (ref "U3")
      (value "TL1963A-33DCQR")
      (footprint "DCQ (R-PDSO-G6)")
      (description "IC REG LINEAR 3.3V 1.5A SOT223-6")
      (fields (field (name "MANUFACTURER") "Texas Instruments"))
      (libsource (lib "ArduinoV1Sch") (part "TL1963A-33DCQR"))
    )
    (comp (ref "U4")
      (value "SN74AHC1G09DBVR")
      (footprint "DVB_SOT_23_5")
      (description "IC GATE AND 1CH 2-INP SOT23-5")
      (fields (field (name "MANUFACTURER") "Texas Instruments"))
      (libsource (lib "ArduinoV1Sch") (part "SN74AHC1G09DBVR"))
    )
    (comp (ref "U5")
      (value "SN74AHC1G09DBVR")
      (footprint "DVB_SOT_23_5")
      (description "IC GATE AND 1CH 2-INP SOT23-5")
      (fields (field (name "MANUFACTURER") "Texas Instruments"))
      (libsource (lib "ArduinoV1Sch") (part "SN74AHC1G09DBVR"))
    )
    (comp (ref "U6")
      (value "SN74AHC1G09DBVR")
      (footprint "DVB_SOT_23_5")
      (description "IC GATE AND 1CH 2-INP SOT23-5")
      (fields (field (name "MANUFACTURER") "Texas Instruments"))
      (libsource (lib "ArduinoV1Sch") (part "SN74AHC1G09DBVR"))
    )
    (comp (ref "U7")
      (value "SN74AHC1G09DBVR")
      (footprint "DVB_SOT_23_5")
      (description "IC GATE AND 1CH 2-INP SOT23-5")
      (fields (field (name "MANUFACTURER") "Texas Instruments"))
      (libsource (lib "ArduinoV1Sch") (part "SN74AHC1G09DBVR"))
    )
    (comp (ref "Y1")
      (value "ABM7-16.000MHZ-D2Y-T")
      (footprint "ABM7_v1_1_BIG")
      (description "CRYSTAL 16.0000MHZ 18PF SMD")
      (fields (field (name "MANUFACTURER") "Abracon") (field (name "TOLERANCE") "20ppm"))
      (libsource (lib "ArduinoV1Sch") (part "ABM7-16.000MHZ-D2Y-T"))
    )
    (comp (ref "Y2")
      (value "ABM7-16.000MHZ-D2Y-T")
      (footprint "ABM7_v1_1_BIG")
      (description "CRYSTAL 16.0000MHZ 18PF SMD")
      (fields (field (name "MANUFACTURER") "Abracon") (field (name "TOLERANCE") "20ppm"))
      (libsource (lib "ArduinoV1Sch") (part "ABM7-16.000MHZ-D2Y-T"))
    )
    (comp (ref "Z1")
      (value "CG0603MLC-05E")
      (footprint "R0603")
      (description "VARISTOR 0603")
      (fields (field (name "MANUFACTURER") "Bourns") (field (name "VOLTAGE") "5V"))
      (libsource (lib "ArduinoV1Sch") (part "CG0603MLC-05E"))
    )
    (comp (ref "Z2")
      (value "CG0603MLC-05E")
      (footprint "R0603")
      (description "VARISTOR 0603")
      (fields (field (name "MANUFACTURER") "Bourns") (field (name "VOLTAGE") "5V"))
      (libsource (lib "ArduinoV1Sch") (part "CG0603MLC-05E"))
    )
  )
  (nets
    (net (code "1") (name "+3V3") (class "Default")
      (node (ref "C13") (pin "2") (pintype "passive"))
      (node (ref "C16") (pin "2") (pinfunction "2_2") (pintype "passive"))
      (node (ref "J1") (pin "4") (pinfunction "4_4") (pintype "passive"))
      (node (ref "JP4") (pin "1") (pinfunction "1_1") (pintype "passive"))
      (node (ref "R28") (pin "2") (pinfunction "2_2") (pintype "passive"))
      (node (ref "U3") (pin "4") (pinfunction "OUT_4") (pintype "passive"))
      (node (ref "U3") (pin "5") (pinfunction "SENSE_5") (pintype "passive"))
    )
    (net (code "2") (name "+5V") (class "Default")
      (node (ref "C12") (pin "2") (pinfunction "2_2") (pintype "passive"))
      (node (ref "C14") (pin "2") (pinfunction "2_2") (pintype "passive"))
      (node (ref "C2") (pin "1") (pinfunction "1_1") (pintype "passive"))
      (node (ref "C6") (pin "1") (pintype "passive"))
      (node (ref "J1") (pin "5") (pinfunction "5_5") (pintype "passive"))
      (node (ref "J8") (pin "1") (pinfunction "1_1") (pintype "passive"))
      (node (ref "JP4") (pin "3") (pinfunction "3_3") (pintype "passive"))
      (node (ref "L1") (pin "2") (pinfunction "2_2") (pintype "passive"))
      (node (ref "R27") (pin "1") (pinfunction "1_1") (pintype "passive"))
      (node (ref "U2") (pin "31") (pinfunction "UVCC_31") (pintype "passive"))
      (node (ref "U3") (pin "1") (pinfunction "~{SHDN}_1") (pintype "passive"))
      (node (ref "U3") (pin "2") (pinfunction "IN_2") (pintype "passive"))
    )
    (net (code "3") (name "+5V{slash}3V3") (class "Default")
      (node (ref "C15") (pin "2") (pinfunction "2_2") (pintype "passive"))
      (node (ref "C17") (pin "2") (pinfunction "2_2") (pintype "passive"))
      (node (ref "C26") (pin "2") (pinfunction "2_2") (pintype "passive"))
      (node (ref "C28") (pin "2") (pinfunction "2_2") (pintype "passive"))
      (node (ref "C29") (pin "2") (pinfunction "2_2") (pintype "passive"))
      (node (ref "C30") (pin "2") (pinfunction "2_2") (pintype "passive"))
      (node (ref "C34") (pin "2") (pintype "passive"))
      (node (ref "C8") (pin "2") (pinfunction "2_2") (pintype "passive"))
      (node (ref "D5") (pin "1") (pinfunction "Cathode_1") (pintype "passive"))
      (node (ref "D6") (pin "1") (pinfunction "Cathode_1") (pintype "passive"))
      (node (ref "FB1") (pin "1") (pinfunction "1_1") (pintype "passive"))
      (node (ref "FB2") (pin "1") (pinfunction "1_1") (pintype "passive"))
      (node (ref "FB3") (pin "1") (pinfunction "1_1") (pintype "passive"))
      (node (ref "J1") (pin "2") (pinfunction "2_2") (pintype "passive"))
      (node (ref "J5") (pin "2") (pinfunction "2_2") (pintype "passive"))
      (node (ref "J6") (pin "2") (pinfunction "2_2") (pintype "passive"))
      (node (ref "JP4") (pin "2") (pinfunction "2_2") (pintype "passive"))
      (node (ref "R1") (pin "2") (pinfunction "2_2") (pintype "passive"))
      (node (ref "R14") (pin "2") (pinfunction "2_2") (pintype "passive"))
      (node (ref "R15") (pin "2") (pinfunction "2_2") (pintype "passive"))
      (node (ref "R17") (pin "2") (pinfunction "2_2") (pintype "passive"))
      (node (ref "R18") (pin "2") (pinfunction "2_2") (pintype "passive"))
      (node (ref "R19") (pin "2") (pinfunction "2_2") (pintype "passive"))
      (node (ref "R2") (pin "2") (pinfunction "2_2") (pintype "passive"))
      (node (ref "R20") (pin "2") (pinfunction "2_2") (pintype "passive"))
      (node (ref "R21") (pin "2") (pinfunction "2_2") (pintype "passive"))
      (node (ref "R27") (pin "2") (pinfunction "2_2") (pintype "passive"))
      (node (ref "R28") (pin "1") (pinfunction "1_1") (pintype "passive"))
      (node (ref "R3") (pin "2") (pinfunction "2_2") (pintype "passive"))
      (node (ref "R4") (pin "2") (pinfunction "2_2") (pintype "passive"))
      (node (ref "U4") (pin "5") (pinfunction "5_5") (pintype "passive"))
      (node (ref "U5") (pin "5") (pinfunction "5_5") (pintype "passive"))
      (node (ref "U6") (pin "5") (pinfunction "5_5") (pintype "passive"))
      (node (ref "U7") (pin "5") (pinfunction "5_5") (pintype "passive"))
    )
    (net (code "4") (name "+AREF") (class "Default")
      (node (ref "C21") (pin "2") (pintype "passive"))
      (node (ref "C24") (pin "1") (pintype "passive"))
      (node (ref "J4") (pin "8") (pinfunction "8_8") (pintype "passive"))
      (node (ref "U1") (pin "21") (pinfunction "AREF_21") (pintype "passive"))
    )
    (net (code "5") (name "/+3V3_16U2_UCAP") (class "Default")
      (node (ref "C7") (pin "2") (pinfunction "2_2") (pintype "passive"))
      (node (ref "R26") (pin "1") (pinfunction "1_1") (pintype "passive"))
      (node (ref "U2") (pin "27") (pinfunction "UCAP_27") (pintype "passive"))
    )
    (net (code "6") (name "/+5V_USB") (class "Default")
      (node (ref "C1") (pin "1") (pinfunction "1_1") (pintype "passive"))
      (node (ref "J7") (pin "1") (pintype "passive"))
      (node (ref "L1") (pin "1") (pinfunction "1_1") (pintype "passive"))
    )
    (net (code "7") (name "/+5V{slash}3V3_16U2") (class "Default")
      (node (ref "C3") (pin "2") (pintype "passive"))
      (node (ref "C4") (pin "1") (pintype "passive"))
      (node (ref "C5") (pin "1") (pintype "passive"))
      (node (ref "FB1") (pin "2") (pinfunction "2_2") (pintype "passive"))
      (node (ref "R26") (pin "2") (pinfunction "2_2") (pintype "passive"))
      (node (ref "U2") (pin "32") (pinfunction "AVCC_32") (pintype "passive"))
      (node (ref "U2") (pin "4") (pinfunction "VCC_4") (pintype "passive"))
    )
    (net (code "8") (name "/+5V{slash}3V3_328P_AVCC") (class "Default")
      (node (ref "C22") (pin "2") (pintype "passive"))
      (node (ref "C23") (pin "1") (pintype "passive"))
      (node (ref "FB3") (pin "2") (pinfunction "2_2") (pintype "passive"))
      (node (ref "U1") (pin "20") (pinfunction "AVCC_20") (pintype "passive"))
    )
    (net (code "9") (name "/+5V{slash}3V3_328P_VCC") (class "Default")
      (node (ref "C19") (pin "2") (pintype "passive"))
      (node (ref "C20") (pin "1") (pintype "passive"))
      (node (ref "FB2") (pin "2") (pinfunction "2_2") (pintype "passive"))
      (node (ref "U1") (pin "7") (pinfunction "VCC_7") (pintype "passive"))
    )
    (net (code "10") (name "/16U2 RESETn") (class "Default")
      (node (ref "JP3") (pin "4") (pinfunction "4_4") (pintype "passive"))
      (node (ref "R4") (pin "1") (pinfunction "1_1") (pintype "passive"))
      (node (ref "U2") (pin "24") (pinfunction "PC1_/_~{RESET}_/_DW_24") (pintype "passive"))
      (node (ref "U5") (pin "4") (pinfunction "4_4") (pintype "passive"))
    )
    (net (code "11") (name "/16U2PROG_328P_RESETn") (class "Default")
      (node (ref "JP1") (pin "2") (pinfunction "2_2") (pintype "passive"))
      (node (ref "R1") (pin "1") (pinfunction "1_1") (pintype "passive"))
      (node (ref "U2") (pin "13") (pinfunction "~{CTS}_/_~{HWB}_/_AIN6_/_T0_/_INT7_/_PD7_13") (pintype "passive"))
    )
    (net (code "12") (name "/16U2_16MHZ_XTAL1") (class "Default")
      (node (ref "C10") (pin "2") (pinfunction "2_2") (pintype "passive"))
      (node (ref "R9") (pin "1") (pinfunction "1_1") (pintype "passive"))
      (node (ref "U2") (pin "1") (pinfunction "XTAL1_1") (pintype "passive"))
      (node (ref "Y2") (pin "1") (pintype "passive"))
    )
    (net (code "13") (name "/16U2_16MHZ_XTAL2") (class "Default")
      (node (ref "C9") (pin "2") (pinfunction "2_2") (pintype "passive"))
      (node (ref "R9") (pin "2") (pinfunction "2_2") (pintype "passive"))
      (node (ref "U2") (pin "2") (pinfunction "XTAL2_/_PC0_2") (pintype "passive"))
      (node (ref "Y2") (pin "2") (pintype "passive"))
    )
    (net (code "14") (name "/16U2_BUF_RESETn") (class "Default")
      (node (ref "C31") (pin "2") (pinfunction "2_2") (pintype "passive"))
      (node (ref "R23") (pin "2") (pinfunction "2_2") (pintype "passive"))
      (node (ref "U5") (pin "1") (pinfunction "1_1") (pintype "passive"))
      (node (ref "U5") (pin "2") (pinfunction "2_2") (pintype "passive"))
    )
    (net (code "15") (name "/16U2_HDR_RESETn") (class "Default")
      (node (ref "J6") (pin "5") (pinfunction "5_5") (pintype "passive"))
      (node (ref "JP3") (pin "3") (pinfunction "3_3") (pintype "passive"))
    )
    (net (code "16") (name "/16U2_MISO") (class "Default")
      (node (ref "J6") (pin "1") (pinfunction "1_1") (pintype "passive"))
      (node (ref "U2") (pin "17") (pinfunction "PDO_/_MISO_/_PCINT3_/_PB3_17") (pintype "passive"))
    )
    (net (code "17") (name "/16U2_MOSI") (class "Default")
      (node (ref "J6") (pin "4") (pinfunction "4_4") (pintype "passive"))
      (node (ref "U2") (pin "16") (pinfunction "PDI_/_MOSI_/_PCINT2_/_PB2_16") (pintype "passive"))
    )
    (net (code "18") (name "/16U2_PB4") (class "Default")
      (node (ref "JP2") (pin "1") (pinfunction "1_1") (pintype "passive"))
      (node (ref "JP3") (pin "2") (pinfunction "2_2") (pintype "passive"))
      (node (ref "U2") (pin "18") (pinfunction "T1_/_PCINT4_/_PB4_18") (pintype "passive"))
    )
    (net (code "19") (name "/16U2_PB5") (class "Default")
      (node (ref "JP2") (pin "3") (pinfunction "3_3") (pintype "passive"))
      (node (ref "U2") (pin "19") (pinfunction "PCINT5_/_PB5_19") (pintype "passive"))
    )
    (net (code "20") (name "/16U2_PB6") (class "Default")
      (node (ref "JP2") (pin "2") (pinfunction "2_2") (pintype "passive"))
      (node (ref "U2") (pin "20") (pinfunction "PCINT6_/_PB6_20") (pintype "passive"))
    )
    (net (code "21") (name "/16U2_PB7") (class "Default")
      (node (ref "JP2") (pin "4") (pinfunction "4_4") (pintype "passive"))
      (node (ref "U2") (pin "21") (pinfunction "OC.0A_/_OC.1C_/_PCINT7_/_PB7_21") (pintype "passive"))
    )
    (net (code "22") (name "/16U2_RXD") (class "Default")
      (node (ref "R11") (pin "1") (pinfunction "1_1") (pintype "passive"))
      (node (ref "U2") (pin "8") (pinfunction "RXD1_/_AIN1_/_INT2_/_PD2_8") (pintype "passive"))
    )
    (net (code "23") (name "/16U2_RX_LED") (class "Default")
      (node (ref "D4") (pin "1") (pinfunction "Cathode_1") (pintype "passive"))
      (node (ref "U2") (pin "10") (pinfunction "AIN3_/_INT5_/_PD4_10") (pintype "passive"))
    )
    (net (code "24") (name "/16U2_SCLK") (class "Default")
      (node (ref "J6") (pin "3") (pinfunction "3_3") (pintype "passive"))
      (node (ref "R5") (pin "2") (pinfunction "2_2") (pintype "passive"))
    )
    (net (code "25") (name "/16U2_SCLK_R") (class "Default")
      (node (ref "R5") (pin "1") (pinfunction "1_1") (pintype "passive"))
      (node (ref "U2") (pin "15") (pinfunction "SCLK_/_PCINT1_/_PB1_15") (pintype "passive"))
    )
    (net (code "26") (name "/16U2_TXD") (class "Default")
      (node (ref "R10") (pin "1") (pinfunction "1_1") (pintype "passive"))
      (node (ref "U2") (pin "9") (pinfunction "TXD1_/_INT3_/_PD3_9") (pintype "passive"))
    )
    (net (code "27") (name "/16U2_TX_LED") (class "Default")
      (node (ref "D3") (pin "1") (pinfunction "Cathode_1") (pintype "passive"))
      (node (ref "U2") (pin "11") (pinfunction "XCK_/_AIN4_/_PCINT12_/_PD5_11") (pintype "passive"))
    )
    (net (code "28") (name "/328P RESETn") (class "Default")
      (node (ref "J1") (pin "3") (pinfunction "3_3") (pintype "passive"))
      (node (ref "J5") (pin "5") (pinfunction "5_5") (pintype "passive"))
      (node (ref "JP3") (pin "1") (pinfunction "1_1") (pintype "passive"))
      (node (ref "R14") (pin "1") (pinfunction "1_1") (pintype "passive"))
      (node (ref "U1") (pin "1") (pinfunction "PC6_/_PCINT14_/_~{RESET}_1") (pintype "passive"))
      (node (ref "U6") (pin "4") (pinfunction "4_4") (pintype "passive"))
    )
    (net (code "29") (name "/328P_16MHZ_XTAL1") (class "Default")
      (node (ref "C27") (pin "2") (pinfunction "2_2") (pintype "passive"))
      (node (ref "R16") (pin "1") (pinfunction "1_1") (pintype "passive"))
      (node (ref "U1") (pin "9") (pinfunction "PB6_/_PCINT6_/_TOSC1_/_XTAL1_9") (pintype "passive"))
      (node (ref "Y1") (pin "1") (pintype "passive"))
    )
    (net (code "30") (name "/328P_16MHZ_XTAL2") (class "Default")
      (node (ref "C25") (pin "2") (pinfunction "2_2") (pintype "passive"))
      (node (ref "R16") (pin "2") (pinfunction "2_2") (pintype "passive"))
      (node (ref "U1") (pin "10") (pinfunction "PB7_/_PCINT7_/_TOSC2_/_XTAL2_10") (pintype "passive"))
      (node (ref "Y1") (pin "2") (pintype "passive"))
    )
    (net (code "31") (name "/328P_AUTORESETn") (class "Default")
      (node (ref "C11") (pin "1") (pintype "passive"))
      (node (ref "R18") (pin "1") (pinfunction "1_1") (pintype "passive"))
      (node (ref "U6") (pin "1") (pinfunction "1_1") (pintype "passive"))
    )
    (net (code "32") (name "/328P_BUF_RESETn") (class "Default")
      (node (ref "C32") (pin "2") (pinfunction "2_2") (pintype "passive"))
      (node (ref "R24") (pin "2") (pinfunction "2_2") (pintype "passive"))
      (node (ref "U6") (pin "2") (pinfunction "2_2") (pintype "passive"))
    )
    (net (code "34") (name "/AD0") (class "Default")
      (node (ref "J2") (pin "1") (pinfunction "1_1") (pintype "passive"))
      (node (ref "U1") (pin "23") (pinfunction "PCINT8_/_ADC0_/_PC0_23") (pintype "passive"))
    )
    (net (code "35") (name "/AD1") (class "Default")
      (node (ref "J2") (pin "2") (pinfunction "2_2") (pintype "passive"))
      (node (ref "U1") (pin "24") (pinfunction "PCINT9_/_ADC1_/_PC1_24") (pintype "passive"))
    )
    (net (code "36") (name "/AD2") (class "Default")
      (node (ref "J2") (pin "3") (pinfunction "3_3") (pintype "passive"))
      (node (ref "U1") (pin "25") (pinfunction "PCINT10_/_ADC2_/_PC2_25") (pintype "passive"))
    )
    (net (code "37") (name "/AD3") (class "Default")
      (node (ref "J2") (pin "4") (pinfunction "4_4") (pintype "passive"))
      (node (ref "U1") (pin "26") (pinfunction "PCINT11_/_ADC3_/_PC3_26") (pintype "passive"))
    )
    (net (code "38") (name "/AD4{slash}SDA") (class "Default")
      (node (ref "J2") (pin "5") (pinfunction "5_5") (pintype "passive"))
      (node (ref "J4") (pin "9") (pinfunction "9_9") (pintype "passive"))
      (node (ref "U1") (pin "27") (pinfunction "SDA_/_PCINT12_/_ADC4_/_PC4_27") (pintype "passive"))
    )
    (net (code "39") (name "/AD5{slash}SCL") (class "Default")
      (node (ref "J2") (pin "6") (pinfunction "6_6") (pintype "passive"))
      (node (ref "J4") (pin "10") (pinfunction "10_10") (pintype "passive"))
      (node (ref "U1") (pin "28") (pinfunction "SCL_/_PCINT13_/_ADC5_/_PC5_28") (pintype "passive"))
    )
    (net (code "40") (name "/BUTTON_RESETn") (class "Default")
      (node (ref "D6") (pin "2") (pinfunction "Anode_2") (pintype "passive"))
      (node (ref "R20") (pin "1") (pinfunction "1_1") (pintype "passive"))
      (node (ref "R24") (pin "1") (pinfunction "1_1") (pintype "passive"))
      (node (ref "SW1") (pin "1") (pintype "passive"))
      (node (ref "SW1") (pin "2") (pintype "passive"))
    )
    (net (code "41") (name "/CON_USB_N") (class "Default")
      (node (ref "J7") (pin "2") (pintype "passive"))
      (node (ref "R6") (pin "1") (pinfunction "1_1") (pintype "passive"))
      (node (ref "Z1") (pin "2") (pinfunction "2_2") (pintype "passive"))
    )
    (net (code "42") (name "/CON_USB_P") (class "Default")
      (node (ref "J7") (pin "3") (pintype "passive"))
      (node (ref "R7") (pin "1") (pinfunction "1_1") (pintype "passive"))
      (node (ref "Z2") (pin "2") (pinfunction "2_2") (pintype "passive"))
    )
    (net (code "43") (name "/IO0") (class "Default")
      (node (ref "J3") (pin "1") (pinfunction "1_1") (pintype "passive"))
      (node (ref "R10") (pin "2") (pinfunction "2_2") (pintype "passive"))
      (node (ref "U1") (pin "2") (pinfunction "RXD_/_PCINT16_/_PD0_2") (pintype "passive"))
    )
    (net (code "44") (name "/IO1") (class "Default")
      (node (ref "J3") (pin "2") (pinfunction "2_2") (pintype "passive"))
      (node (ref "R11") (pin "2") (pinfunction "2_2") (pintype "passive"))
      (node (ref "U1") (pin "3") (pinfunction "TXD_/_PCINT17_/_PD1_3") (pintype "passive"))
    )
    (net (code "45") (name "/IO2") (class "Default")
      (node (ref "J3") (pin "3") (pinfunction "3_3") (pintype "passive"))
      (node (ref "U1") (pin "4") (pinfunction "INT0_/_PCINT18_/_PD2_4") (pintype "passive"))
    )
    (net (code "46") (name "/IO3") (class "Default")
      (node (ref "J3") (pin "4") (pinfunction "4_4") (pintype "passive"))
      (node (ref "U1") (pin "5") (pinfunction "INT1_/_OC2B__/_PCINT19_/_PD3_5") (pintype "passive"))
    )
    (net (code "47") (name "/IO4") (class "Default")
      (node (ref "J3") (pin "5") (pinfunction "5_5") (pintype "passive"))
      (node (ref "U1") (pin "6") (pinfunction "XCK_/_T0_/_PCINT20_/_PD4_6") (pintype "passive"))
    )
    (net (code "48") (name "/IO5") (class "Default")
      (node (ref "J3") (pin "6") (pinfunction "6_6") (pintype "passive"))
      (node (ref "U1") (pin "11") (pinfunction "OC0B_/_T1_/_PCINT21_/_PD5_11") (pintype "passive"))
    )
    (net (code "49") (name "/IO6") (class "Default")
      (node (ref "J3") (pin "7") (pinfunction "7_7") (pintype "passive"))
      (node (ref "U1") (pin "12") (pinfunction "OC0A_/_AIN0_/_PCINT22_/_PD6_12") (pintype "passive"))
    )
    (net (code "50") (name "/IO7") (class "Default")
      (node (ref "J3") (pin "8") (pinfunction "8_8") (pintype "passive"))
      (node (ref "U1") (pin "13") (pinfunction "AIN1_/_PCINT23_/_PD7_13") (pintype "passive"))
    )
    (net (code "51") (name "/IO8") (class "Default")
      (node (ref "J4") (pin "1") (pinfunction "1_1") (pintype "passive"))
      (node (ref "R22") (pin "2") (pinfunction "2_2") (pintype "passive"))
      (node (ref "U1") (pin "14") (pinfunction "CLKO_/_ICP1_/_PCINT0_/_PB0_14") (pintype "passive"))
    )
    (net (code "52") (name "/IO9") (class "Default")
      (node (ref "J4") (pin "2") (pinfunction "2_2") (pintype "passive"))
      (node (ref "U1") (pin "15") (pinfunction "OCIA_/_PCINT1_/_PB1_15") (pintype "passive"))
    )
    (net (code "53") (name "/MISO") (class "Default")
      (node (ref "J4") (pin "5") (pinfunction "5_5") (pintype "passive"))
      (node (ref "J5") (pin "1") (pinfunction "1_1") (pintype "passive"))
      (node (ref "U1") (pin "18") (pinfunction "MISO_/_PCINT4_/_PB4_18") (pintype "passive"))
    )
    (net (code "54") (name "/MOSI") (class "Default")
      (node (ref "J4") (pin "4") (pinfunction "4_4") (pintype "passive"))
      (node (ref "J5") (pin "4") (pinfunction "4_4") (pintype "passive"))
      (node (ref "U1") (pin "17") (pinfunction "MOSI_/_OC2A_/_PCINT3_/_PB3_17") (pintype "passive"))
    )
    (net (code "55") (name "/SCK") (class "Default")
      (node (ref "J4") (pin "6") (pinfunction "6_6") (pintype "passive"))
      (node (ref "J5") (pin "3") (pinfunction "3_3") (pintype "passive"))
      (node (ref "R13") (pin "2") (pinfunction "2_2") (pintype "passive"))
      (node (ref "U4") (pin "1") (pinfunction "1_1") (pintype "passive"))
      (node (ref "U4") (pin "2") (pinfunction "2_2") (pintype "passive"))
    )
    (net (code "56") (name "/SCK_R") (class "Default")
      (node (ref "R13") (pin "1") (pinfunction "1_1") (pintype "passive"))
      (node (ref "U1") (pin "19") (pinfunction "SCK_/_PCINT5_/_PB5_19") (pintype "passive"))
    )
    (net (code "57") (name "/SS") (class "Default")
      (node (ref "J4") (pin "3") (pinfunction "3_3") (pintype "passive"))
      (node (ref "U1") (pin "16") (pinfunction "~{SS}_/_OCIB_/_PCINT2_/_PB2_16") (pintype "passive"))
    )
    (net (code "58") (name "/USB_N") (class "Default")
      (node (ref "R6") (pin "2") (pinfunction "2_2") (pintype "passive"))
      (node (ref "U2") (pin "30") (pinfunction "D-_30") (pintype "passive"))
    )
    (net (code "59") (name "/USB_P") (class "Default")
      (node (ref "R7") (pin "2") (pinfunction "2_2") (pintype "passive"))
      (node (ref "U2") (pin "29") (pinfunction "D+_29") (pintype "passive"))
    )
    (net (code "60") (name "/USER_BUTTON") (class "Default")
      (node (ref "R21") (pin "1") (pinfunction "1_1") (pintype "passive"))
      (node (ref "R25") (pin "1") (pinfunction "1_1") (pintype "passive"))
      (node (ref "SW2") (pin "1") (pintype "passive"))
      (node (ref "SW2") (pin "2") (pintype "passive"))
    )
    (net (code "61") (name "/USER_BUTTON_BUF") (class "Default")
      (node (ref "C33") (pin "2") (pinfunction "2_2") (pintype "passive"))
      (node (ref "R25") (pin "2") (pinfunction "2_2") (pintype "passive"))
      (node (ref "U7") (pin "1") (pinfunction "1_1") (pintype "passive"))
      (node (ref "U7") (pin "2") (pinfunction "2_2") (pintype "passive"))
    )
    (net (code "62") (name "GND") (class "Default")
      (node (ref "C1") (pin "2") (pinfunction "2_2") (pintype "passive"))
      (node (ref "C10") (pin "1") (pintype "passive"))
      (node (ref "C12") (pin "1") (pintype "passive"))
      (node (ref "C13") (pin "1") (pintype "passive"))
      (node (ref "C14") (pin "1") (pintype "passive"))
      (node (ref "C15") (pin "1") (pintype "passive"))
      (node (ref "C16") (pin "1") (pintype "passive"))
      (node (ref "C17") (pin "1") (pintype "passive"))
      (node (ref "C19") (pin "1") (pintype "passive"))
      (node (ref "C2") (pin "2") (pinfunction "2_2") (pintype "passive"))
      (node (ref "C20") (pin "2") (pinfunction "2_2") (pintype "passive"))
      (node (ref "C21") (pin "1") (pintype "passive"))
      (node (ref "C22") (pin "1") (pintype "passive"))
      (node (ref "C23") (pin "2") (pinfunction "2_2") (pintype "passive"))
      (node (ref "C24") (pin "2") (pinfunction "2_2") (pintype "passive"))
      (node (ref "C25") (pin "1") (pintype "passive"))
      (node (ref "C26") (pin "1") (pintype "passive"))
      (node (ref "C27") (pin "1") (pintype "passive"))
      (node (ref "C28") (pin "1") (pintype "passive"))
      (node (ref "C29") (pin "1") (pintype "passive"))
      (node (ref "C3") (pin "1") (pintype "passive"))
      (node (ref "C30") (pin "1") (pintype "passive"))
      (node (ref "C31") (pin "1") (pintype "passive"))
      (node (ref "C32") (pin "1") (pintype "passive"))
      (node (ref "C33") (pin "1") (pintype "passive"))
      (node (ref "C34") (pin "1") (pintype "passive"))
      (node (ref "C4") (pin "2") (pinfunction "2_2") (pintype "passive"))
      (node (ref "C5") (pin "2") (pinfunction "2_2") (pintype "passive"))
      (node (ref "C6") (pin "2") (pinfunction "2_2") (pintype "passive"))
      (node (ref "C7") (pin "1") (pinfunction "1_1") (pintype "passive"))
      (node (ref "C8") (pin "1") (pintype "passive"))
      (node (ref "C9") (pin "1") (pintype "passive"))
      (node (ref "D1") (pin "1") (pinfunction "Cathode_1") (pintype "passive"))
      (node (ref "J1") (pin "6") (pinfunction "6_6") (pintype "passive"))
      (node (ref "J1") (pin "7") (pinfunction "7_7") (pintype "passive"))
      (node (ref "J4") (pin "7") (pinfunction "7_7") (pintype "passive"))
      (node (ref "J5") (pin "6") (pinfunction "6_6") (pintype "passive"))
      (node (ref "J6") (pin "6") (pinfunction "6_6") (pintype "passive"))
      (node (ref "J7") (pin "10") (pintype "passive"))
      (node (ref "J7") (pin "11") (pintype "passive"))
      (node (ref "J7") (pin "5") (pintype "passive"))
      (node (ref "J7") (pin "6") (pintype "passive"))
      (node (ref "J7") (pin "7") (pintype "passive"))
      (node (ref "J7") (pin "8") (pintype "passive"))
      (node (ref "J7") (pin "9") (pintype "passive"))
      (node (ref "J9") (pin "1") (pinfunction "1_1") (pintype "passive"))
      (node (ref "MH1") (pin "1") (pinfunction "1_1") (pintype "passive"))
      (node (ref "MH2") (pin "1") (pinfunction "1_1") (pintype "passive"))
      (node (ref "MH3") (pin "1") (pinfunction "1_1") (pintype "passive"))
      (node (ref "R12") (pin "1") (pinfunction "1_1") (pintype "passive"))
      (node (ref "R8") (pin "2") (pinfunction "2_2") (pintype "passive"))
      (node (ref "SW1") (pin "3") (pintype "passive"))
      (node (ref "SW1") (pin "4") (pintype "passive"))
      (node (ref "SW2") (pin "3") (pintype "passive"))
      (node (ref "SW2") (pin "4") (pintype "passive"))
      (node (ref "U1") (pin "22") (pinfunction "GND_2_22") (pintype "passive"))
      (node (ref "U1") (pin "8") (pinfunction "GND_1_8") (pintype "passive"))
      (node (ref "U2") (pin "28") (pinfunction "UGND_28") (pintype "passive"))
      (node (ref "U2") (pin "3") (pinfunction "GND_3") (pintype "passive"))
      (node (ref "U3") (pin "3") (pinfunction "GND_3") (pintype "passive"))
      (node (ref "U3") (pin "6") (pinfunction "EPAD_6") (pintype "passive"))
      (node (ref "U4") (pin "3") (pinfunction "3_3") (pintype "passive"))
      (node (ref "U5") (pin "3") (pinfunction "3_3") (pintype "passive"))
      (node (ref "U6") (pin "3") (pinfunction "3_3") (pintype "passive"))
      (node (ref "U7") (pin "3") (pinfunction "3_3") (pintype "passive"))
      (node (ref "Z1") (pin "1") (pinfunction "1_1") (pintype "passive"))
      (node (ref "Z2") (pin "1") (pinfunction "1_1") (pintype "passive"))
    )
    (net (code "63") (name "Net-(C11-Pad2)") (class "Default")
      (node (ref "C11") (pin "2") (pinfunction "2_2") (pintype "passive"))
      (node (ref "JP1") (pin "1") (pinfunction "1_1") (pintype "passive"))
    )
    (net (code "64") (name "Net-(D1-Anode)") (class "Default")
      (node (ref "D1") (pin "2") (pinfunction "Anode_2") (pintype "passive"))
      (node (ref "R17") (pin "1") (pinfunction "1_1") (pintype "passive"))
    )
    (net (code "65") (name "Net-(D2-Anode)") (class "Default")
      (node (ref "D2") (pin "2") (pinfunction "Anode_2") (pintype "passive"))
      (node (ref "R15") (pin "1") (pinfunction "1_1") (pintype "passive"))
    )
    (net (code "66") (name "Net-(D2-Cathode)") (class "Default")
      (node (ref "D2") (pin "1") (pinfunction "Cathode_1") (pintype "passive"))
      (node (ref "U4") (pin "4") (pinfunction "4_4") (pintype "passive"))
    )
    (net (code "67") (name "Net-(D3-Anode)") (class "Default")
      (node (ref "D3") (pin "2") (pinfunction "Anode_2") (pintype "passive"))
      (node (ref "R2") (pin "1") (pinfunction "1_1") (pintype "passive"))
    )
    (net (code "68") (name "Net-(D4-Anode)") (class "Default")
      (node (ref "D4") (pin "2") (pinfunction "Anode_2") (pintype "passive"))
      (node (ref "R3") (pin "1") (pinfunction "1_1") (pintype "passive"))
    )
    (net (code "69") (name "Net-(D5-Anode)") (class "Default")
      (node (ref "D5") (pin "2") (pinfunction "Anode_2") (pintype "passive"))
      (node (ref "R19") (pin "1") (pinfunction "1_1") (pintype "passive"))
      (node (ref "R23") (pin "1") (pinfunction "1_1") (pintype "passive"))
    )
    (net (code "70") (name "Net-(J7-Pad4)") (class "Default")
      (node (ref "J7") (pin "4") (pintype "passive"))
      (node (ref "R8") (pin "1") (pinfunction "1_1") (pintype "passive"))
    )
    (net (code "71") (name "Net-(JP1-Pad3)") (class "Default")
      (node (ref "JP1") (pin "3") (pinfunction "3_3") (pintype "passive"))
      (node (ref "R12") (pin "2") (pinfunction "2_2") (pintype "passive"))
    )
    (net (code "72") (name "Net-(R22-Pad1)") (class "Default")
      (node (ref "R22") (pin "1") (pinfunction "1_1") (pintype "passive"))
      (node (ref "U7") (pin "4") (pinfunction "4_4") (pintype "passive"))
    )
    (net (code "73") (name "unconnected-(J1-Pad1)") (class "Default")
      (node (ref "J1") (pin "1") (pinfunction "1_1") (pintype "passive+no_connect"))
    )
    (net (code "74") (name "unconnected-(J1-Pad8)") (class "Default")
      (node (ref "J1") (pin "8") (pinfunction "8_8") (pintype "passive+no_connect"))
    )
    (net (code "75") (name "unconnected-(MH4-Pad1)") (class "Default")
      (node (ref "MH4") (pin "1") (pinfunction "1_1") (pintype "passive"))
    )
    (net (code "76") (name "unconnected-(U2-AIN0_{slash}_INT1_{slash}_PD1-Pad7)") (class "Default")
      (node (ref "U2") (pin "7") (pinfunction "AIN0_/_INT1_/_PD1_7") (pintype "passive+no_connect"))
    )
    (net (code "77") (name "unconnected-(U2-AIN2_{slash}_PCINT11_{slash}_PC2-Pad5)") (class "Default")
      (node (ref "U2") (pin "5") (pinfunction "AIN2_/_PCINT11_/_PC2_5") (pintype "passive+no_connect"))
    )
    (net (code "78") (name "unconnected-(U2-CLKO_{slash}_ICP1_{slash}_INT4_{slash}_PC7-Pad22)") (class "Default")
      (node (ref "U2") (pin "22") (pinfunction "CLKO_/_ICP1_/_INT4_/_PC7_22") (pintype "passive+no_connect"))
    )
    (net (code "79") (name "unconnected-(U2-OC.0B_{slash}_INT0_{slash}_PD0-Pad6)") (class "Default")
      (node (ref "U2") (pin "6") (pinfunction "OC.0B_/_INT0_/_PD0_6") (pintype "passive+no_connect"))
    )
    (net (code "80") (name "unconnected-(U2-OC.1A_{slash}_PCINT8_{slash}_PC6-Pad23)") (class "Default")
      (node (ref "U2") (pin "23") (pinfunction "OC.1A_/_PCINT8_/_PC6_23") (pintype "passive+no_connect"))
    )
    (net (code "81") (name "unconnected-(U2-OC.1B_{slash}_PCINT9_{slash}_PC5-Pad25)") (class "Default")
      (node (ref "U2") (pin "25") (pinfunction "OC.1B_/_PCINT9_/_PC5_25") (pintype "passive+no_connect"))
    )
    (net (code "82") (name "unconnected-(U2-PCINT10_{slash}_PC4-Pad26)") (class "Default")
      (node (ref "U2") (pin "26") (pinfunction "PCINT10_/_PC4_26") (pintype "passive+no_connect"))
    )
    (net (code "83") (name "unconnected-(U2-~{RTS}_{slash}_AIN5_{slash}_INT6_{slash}_PD6-Pad12)") (class "Default")
      (node (ref "U2") (pin "12") (pinfunction "~{RTS}_/_AIN5_/_INT6_/_PD6_12") (pintype "passive+no_connect"))
    )
    (net (code "84") (name "unconnected-(U2-~{SS}_{slash}_PCINT0_{slash}_PB0-Pad14)") (class "Default")
      (node (ref "U2") (pin "14") (pinfunction "~{SS}_/_PCINT0_/_PB0_14") (pintype "passive+no_connect"))
    )
  )
)
